# ece411_t2_schematic_8.net
KiCad netlist of a schematic drawn in EAGLE
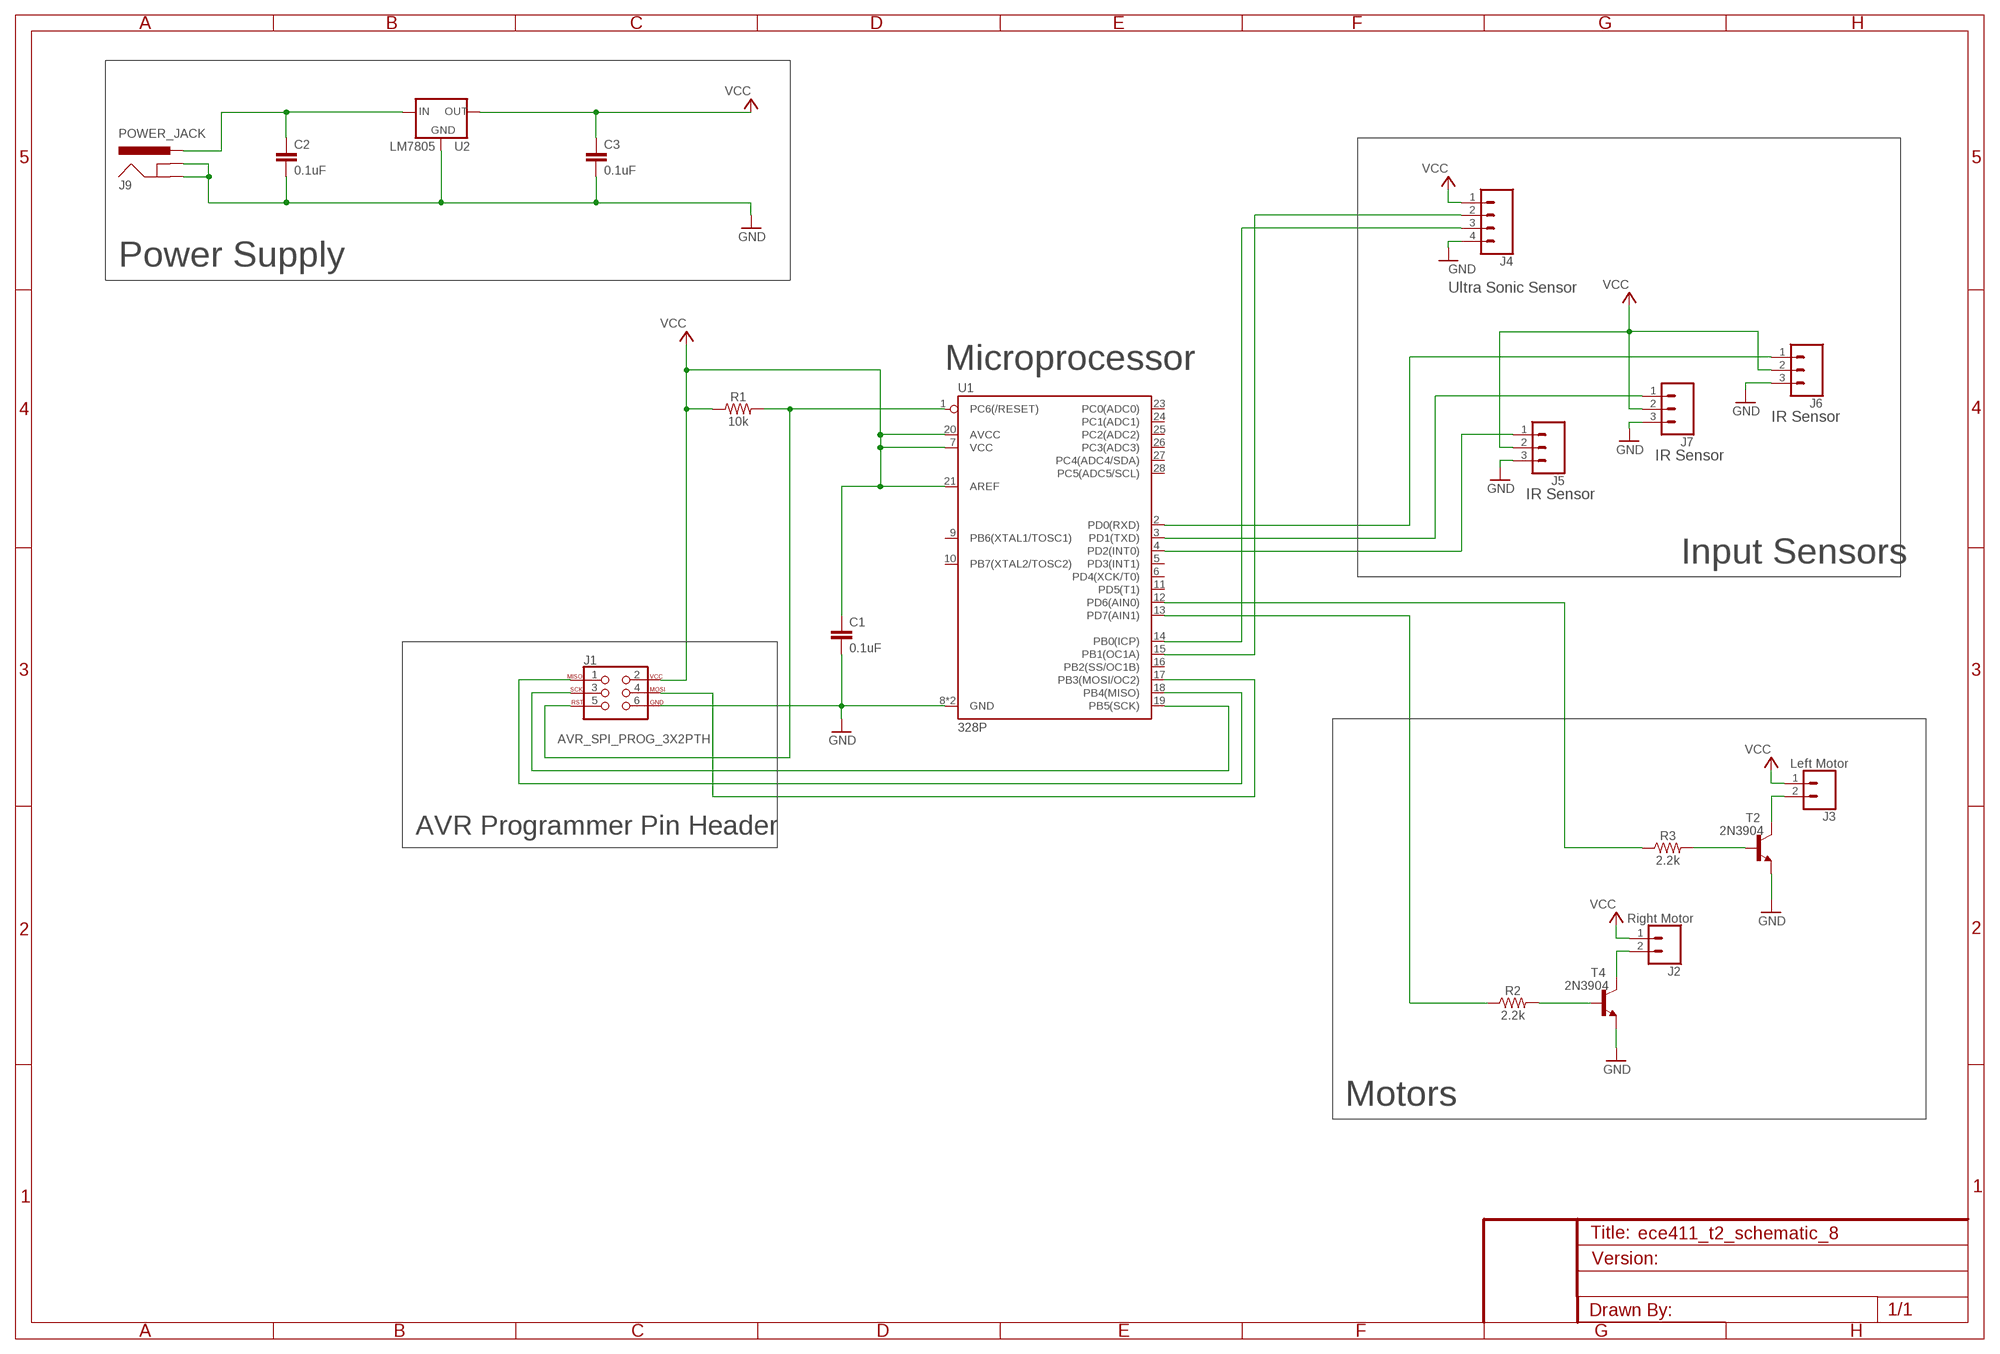
[diagram p0: schematic, sheet 1]

(export (version "E")
  (design (tool "Eeschema 10.0.6"))
  (components
    (comp (ref "C1")
      (value "0.1uF")
      (footprint "eagle-import:0402")
      (libsource (lib "eagle-import") (part "0.1UF-0402-6.3V-10%-X7R"))
    )
    (comp (ref "C2")
      (value "0.1uF")
      (footprint "eagle-import:0402")
      (libsource (lib "eagle-import") (part "0.1UF-0402-6.3V-10%-X7R"))
    )
    (comp (ref "C3")
      (value "0.1uF")
      (footprint "eagle-import:0402")
      (libsource (lib "eagle-import") (part "0.1UF-0402-6.3V-10%-X7R"))
    )
    (comp (ref "J1")
      (value "AVR_SPI_PROG_3X2PTH")
      (footprint "eagle-import:2X3")
      (libsource (lib "eagle-import") (part "AVR_SPI_PROG_3X2PTH"))
    )
    (comp (ref "J2")
      (value "Right Motor")
      (footprint "eagle-import:1X02")
      (libsource (lib "eagle-import") (part "CONN_02"))
    )
    (comp (ref "J3")
      (value "Left Motor")
      (footprint "eagle-import:1X02")
      (libsource (lib "eagle-import") (part "CONN_02"))
    )
    (comp (ref "J4")
      (value "CONN_04")
      (footprint "eagle-import:1X04")
      (libsource (lib "eagle-import") (part "CONN_04"))
    )
    (comp (ref "J5")
      (value "455-1750-1-ND")
      (footprint "eagle-import:1X03")
      (libsource (lib "eagle-import") (part "CONN_03"))
    )
    (comp (ref "J6")
      (value "455-1750-1-ND")
      (footprint "eagle-import:1X03")
      (libsource (lib "eagle-import") (part "CONN_03"))
    )
    (comp (ref "J7")
      (value "455-1750-1-ND")
      (footprint "eagle-import:1X03")
      (libsource (lib "eagle-import") (part "CONN_03"))
    )
    (comp (ref "J9")
      (value "POWER_JACK")
      (footprint "eagle-import:POWER_JACK_PTH")
      (libsource (lib "eagle-import") (part "POWER_JACK"))
    )
    (comp (ref "R1")
      (value "10k")
      (footprint "eagle-import:0402")
      (libsource (lib "eagle-import") (part "10KOHM-0402-1/16W-1%"))
    )
    (comp (ref "R2")
      (value "2.2k")
      (footprint "eagle-import:0603")
      (libsource (lib "eagle-import") (part "2.2KOHM-0603-1/10W-1%"))
    )
    (comp (ref "R3")
      (value "2.2k")
      (footprint "eagle-import:0603")
      (libsource (lib "eagle-import") (part "2.2KOHM-0603-1/10W-1%"))
    )
    (comp (ref "T2")
      (value "2N3904")
      (footprint "eagle-import:TO92")
      (libsource (lib "eagle-import") (part "2N3904"))
    )
    (comp (ref "T4")
      (value "2N3904")
      (footprint "eagle-import:TO92")
      (libsource (lib "eagle-import") (part "2N3904"))
    )
    (comp (ref "U1")
      (value "328P")
      (footprint "eagle-import:DIP28")
      (libsource (lib "eagle-import") (part "ATMEGA328P_PDIP"))
    )
    (comp (ref "U2")
      (value "LM7805")
      (footprint "eagle-import:TO-220-ALT")
      (libsource (lib "eagle-import") (part "V_REG_78XX-TO-220"))
    )
  )
  (nets
    (net (code "1") (name "GND") (class "Default")
      (node (ref "C1") (pin "2") (pinfunction "2_2") (pintype "passive"))
      (node (ref "C2") (pin "2") (pinfunction "2_2") (pintype "passive"))
      (node (ref "C3") (pin "2") (pinfunction "2_2") (pintype "passive"))
      (node (ref "J1") (pin "6") (pinfunction "6_6") (pintype "passive"))
      (node (ref "J4") (pin "4") (pinfunction "4_4") (pintype "passive"))
      (node (ref "J5") (pin "3") (pinfunction "3_3") (pintype "passive"))
      (node (ref "J6") (pin "3") (pinfunction "3_3") (pintype "passive"))
      (node (ref "J7") (pin "3") (pinfunction "3_3") (pintype "passive"))
      (node (ref "J9") (pin "GND") (pinfunction "GND_GND") (pintype "bidirectional"))
      (node (ref "J9") (pin "GNDBREAK") (pinfunction "GNDBREAK_GNDBREAK") (pintype "bidirectional"))
      (node (ref "T2") (pin "3") (pinfunction "E_3") (pintype "passive"))
      (node (ref "T4") (pin "3") (pinfunction "E_3") (pintype "passive"))
      (node (ref "U1") (pin "22") (pinfunction "GND_22") (pintype "bidirectional"))
      (node (ref "U1") (pin "8") (pinfunction "GND_8") (pintype "bidirectional"))
      (node (ref "U2") (pin "GND") (pinfunction "GND_GND") (pintype "input"))
    )
    (net (code "2") (name "Net-(C2-Pad1)") (class "Default")
      (node (ref "C2") (pin "1") (pinfunction "1_1") (pintype "passive"))
      (node (ref "J9") (pin "PWR") (pinfunction "PWR_PWR") (pintype "bidirectional"))
      (node (ref "U2") (pin "IN") (pinfunction "IN_IN") (pintype "input"))
    )
    (net (code "3") (name "Net-(T2-B)") (class "Default")
      (node (ref "R3") (pin "2") (pinfunction "2_2") (pintype "passive"))
      (node (ref "T2") (pin "2") (pinfunction "B_2") (pintype "passive"))
    )
    (net (code "4") (name "Net-(T2-C)") (class "Default")
      (node (ref "J3") (pin "2") (pinfunction "2_2") (pintype "passive"))
      (node (ref "T2") (pin "1") (pinfunction "C_1") (pintype "passive"))
    )
    (net (code "5") (name "Net-(T4-B)") (class "Default")
      (node (ref "R2") (pin "2") (pinfunction "2_2") (pintype "passive"))
      (node (ref "T4") (pin "2") (pinfunction "B_2") (pintype "passive"))
    )
    (net (code "6") (name "Net-(T4-C)") (class "Default")
      (node (ref "J2") (pin "2") (pinfunction "2_2") (pintype "passive"))
      (node (ref "T4") (pin "1") (pinfunction "C_1") (pintype "passive"))
    )
    (net (code "7") (name "Net-(U1-PB0(ICP))") (class "Default")
      (node (ref "J4") (pin "3") (pinfunction "3_3") (pintype "passive"))
      (node (ref "U1") (pin "14") (pinfunction "PB0(ICP)_14") (pintype "bidirectional"))
    )
    (net (code "8") (name "Net-(U1-PB1(OC1A))") (class "Default")
      (node (ref "J4") (pin "2") (pinfunction "2_2") (pintype "passive"))
      (node (ref "U1") (pin "15") (pinfunction "PB1(OC1A)_15") (pintype "bidirectional"))
    )
    (net (code "9") (name "Net-(U1-PB3(MOSI{slash}OC2))") (class "Default")
      (node (ref "J1") (pin "4") (pinfunction "4_4") (pintype "passive"))
      (node (ref "U1") (pin "17") (pinfunction "PB3(MOSI/OC2)_17") (pintype "bidirectional"))
    )
    (net (code "10") (name "Net-(U1-PB4(MISO))") (class "Default")
      (node (ref "J1") (pin "1") (pinfunction "1_1") (pintype "passive"))
      (node (ref "U1") (pin "18") (pinfunction "PB4(MISO)_18") (pintype "bidirectional"))
    )
    (net (code "11") (name "Net-(U1-PB5(SCK))") (class "Default")
      (node (ref "J1") (pin "3") (pinfunction "3_3") (pintype "passive"))
      (node (ref "U1") (pin "19") (pinfunction "PB5(SCK)_19") (pintype "bidirectional"))
    )
    (net (code "12") (name "Net-(U1-PC6({slash}RESET))") (class "Default")
      (node (ref "J1") (pin "5") (pinfunction "5_5") (pintype "passive"))
      (node (ref "R1") (pin "2") (pinfunction "2_2") (pintype "passive"))
      (node (ref "U1") (pin "1") (pinfunction "PC6(/RESET)_1") (pintype "bidirectional"))
    )
    (net (code "13") (name "Net-(U1-PD0(RXD))") (class "Default")
      (node (ref "J6") (pin "1") (pinfunction "1_1") (pintype "passive"))
      (node (ref "U1") (pin "2") (pinfunction "PD0(RXD)_2") (pintype "bidirectional"))
    )
    (net (code "14") (name "Net-(U1-PD1(TXD))") (class "Default")
      (node (ref "J7") (pin "1") (pinfunction "1_1") (pintype "passive"))
      (node (ref "U1") (pin "3") (pinfunction "PD1(TXD)_3") (pintype "bidirectional"))
    )
    (net (code "15") (name "Net-(U1-PD2(INT0))") (class "Default")
      (node (ref "J5") (pin "1") (pinfunction "1_1") (pintype "passive"))
      (node (ref "U1") (pin "4") (pinfunction "PD2(INT0)_4") (pintype "bidirectional"))
    )
    (net (code "16") (name "Net-(U1-PD6(AIN0))") (class "Default")
      (node (ref "R3") (pin "1") (pinfunction "1_1") (pintype "passive"))
      (node (ref "U1") (pin "12") (pinfunction "PD6(AIN0)_12") (pintype "bidirectional"))
    )
    (net (code "17") (name "Net-(U1-PD7(AIN1))") (class "Default")
      (node (ref "R2") (pin "1") (pinfunction "1_1") (pintype "passive"))
      (node (ref "U1") (pin "13") (pinfunction "PD7(AIN1)_13") (pintype "bidirectional"))
    )
    (net (code "18") (name "VCC") (class "Default")
      (node (ref "C1") (pin "1") (pinfunction "1_1") (pintype "passive"))
      (node (ref "C3") (pin "1") (pinfunction "1_1") (pintype "passive"))
      (node (ref "J1") (pin "2") (pinfunction "2_2") (pintype "passive"))
      (node (ref "J2") (pin "1") (pinfunction "1_1") (pintype "passive"))
      (node (ref "J3") (pin "1") (pinfunction "1_1") (pintype "passive"))
      (node (ref "J4") (pin "1") (pinfunction "1_1") (pintype "passive"))
      (node (ref "J5") (pin "2") (pinfunction "2_2") (pintype "passive"))
      (node (ref "J6") (pin "2") (pinfunction "2_2") (pintype "passive"))
      (node (ref "J7") (pin "2") (pinfunction "2_2") (pintype "passive"))
      (node (ref "R1") (pin "1") (pinfunction "1_1") (pintype "passive"))
      (node (ref "U1") (pin "20") (pinfunction "AVCC_20") (pintype "bidirectional"))
      (node (ref "U1") (pin "21") (pinfunction "AREF_21") (pintype "bidirectional"))
      (node (ref "U1") (pin "7") (pinfunction "VCC_7") (pintype "bidirectional"))
      (node (ref "U2") (pin "OUT") (pinfunction "OUT_OUT") (pintype "passive"))
    )
    (net (code "19") (name "unconnected-(U1-PB2(SS{slash}OC1B)-Pad16)") (class "Default")
      (node (ref "U1") (pin "16") (pinfunction "PB2(SS/OC1B)_16") (pintype "bidirectional"))
    )
    (net (code "20") (name "unconnected-(U1-PB6(XTAL1{slash}TOSC1)-Pad9)") (class "Default")
      (node (ref "U1") (pin "9") (pinfunction "PB6(XTAL1/TOSC1)_9") (pintype "bidirectional"))
    )
    (net (code "21") (name "unconnected-(U1-PB7(XTAL2{slash}TOSC2)-Pad10)") (class "Default")
      (node (ref "U1") (pin "10") (pinfunction "PB7(XTAL2/TOSC2)_10") (pintype "bidirectional"))
    )
    (net (code "22") (name "unconnected-(U1-PC0(ADC0)-Pad23)") (class "Default")
      (node (ref "U1") (pin "23") (pinfunction "PC0(ADC0)_23") (pintype "bidirectional"))
    )
    (net (code "23") (name "unconnected-(U1-PC1(ADC1)-Pad24)") (class "Default")
      (node (ref "U1") (pin "24") (pinfunction "PC1(ADC1)_24") (pintype "bidirectional"))
    )
    (net (code "24") (name "unconnected-(U1-PC2(ADC2)-Pad25)") (class "Default")
      (node (ref "U1") (pin "25") (pinfunction "PC2(ADC2)_25") (pintype "bidirectional"))
    )
    (net (code "25") (name "unconnected-(U1-PC3(ADC3)-Pad26)") (class "Default")
      (node (ref "U1") (pin "26") (pinfunction "PC3(ADC3)_26") (pintype "bidirectional"))
    )
    (net (code "26") (name "unconnected-(U1-PC4(ADC4{slash}SDA)-Pad27)") (class "Default")
      (node (ref "U1") (pin "27") (pinfunction "PC4(ADC4/SDA)_27") (pintype "bidirectional"))
    )
    (net (code "27") (name "unconnected-(U1-PC5(ADC5{slash}SCL)-Pad28)") (class "Default")
      (node (ref "U1") (pin "28") (pinfunction "PC5(ADC5/SCL)_28") (pintype "bidirectional"))
    )
    (net (code "28") (name "unconnected-(U1-PD3(INT1)-Pad5)") (class "Default")
      (node (ref "U1") (pin "5") (pinfunction "PD3(INT1)_5") (pintype "bidirectional"))
    )
    (net (code "29") (name "unconnected-(U1-PD4(XCK{slash}T0)-Pad6)") (class "Default")
      (node (ref "U1") (pin "6") (pinfunction "PD4(XCK/T0)_6") (pintype "bidirectional"))
    )
    (net (code "30") (name "unconnected-(U1-PD5(T1)-Pad11)") (class "Default")
      (node (ref "U1") (pin "11") (pinfunction "PD5(T1)_11") (pintype "bidirectional"))
    )
  )
)
